# GateAmp.net
KiCad netlist of a schematic drawn in Altium Designer
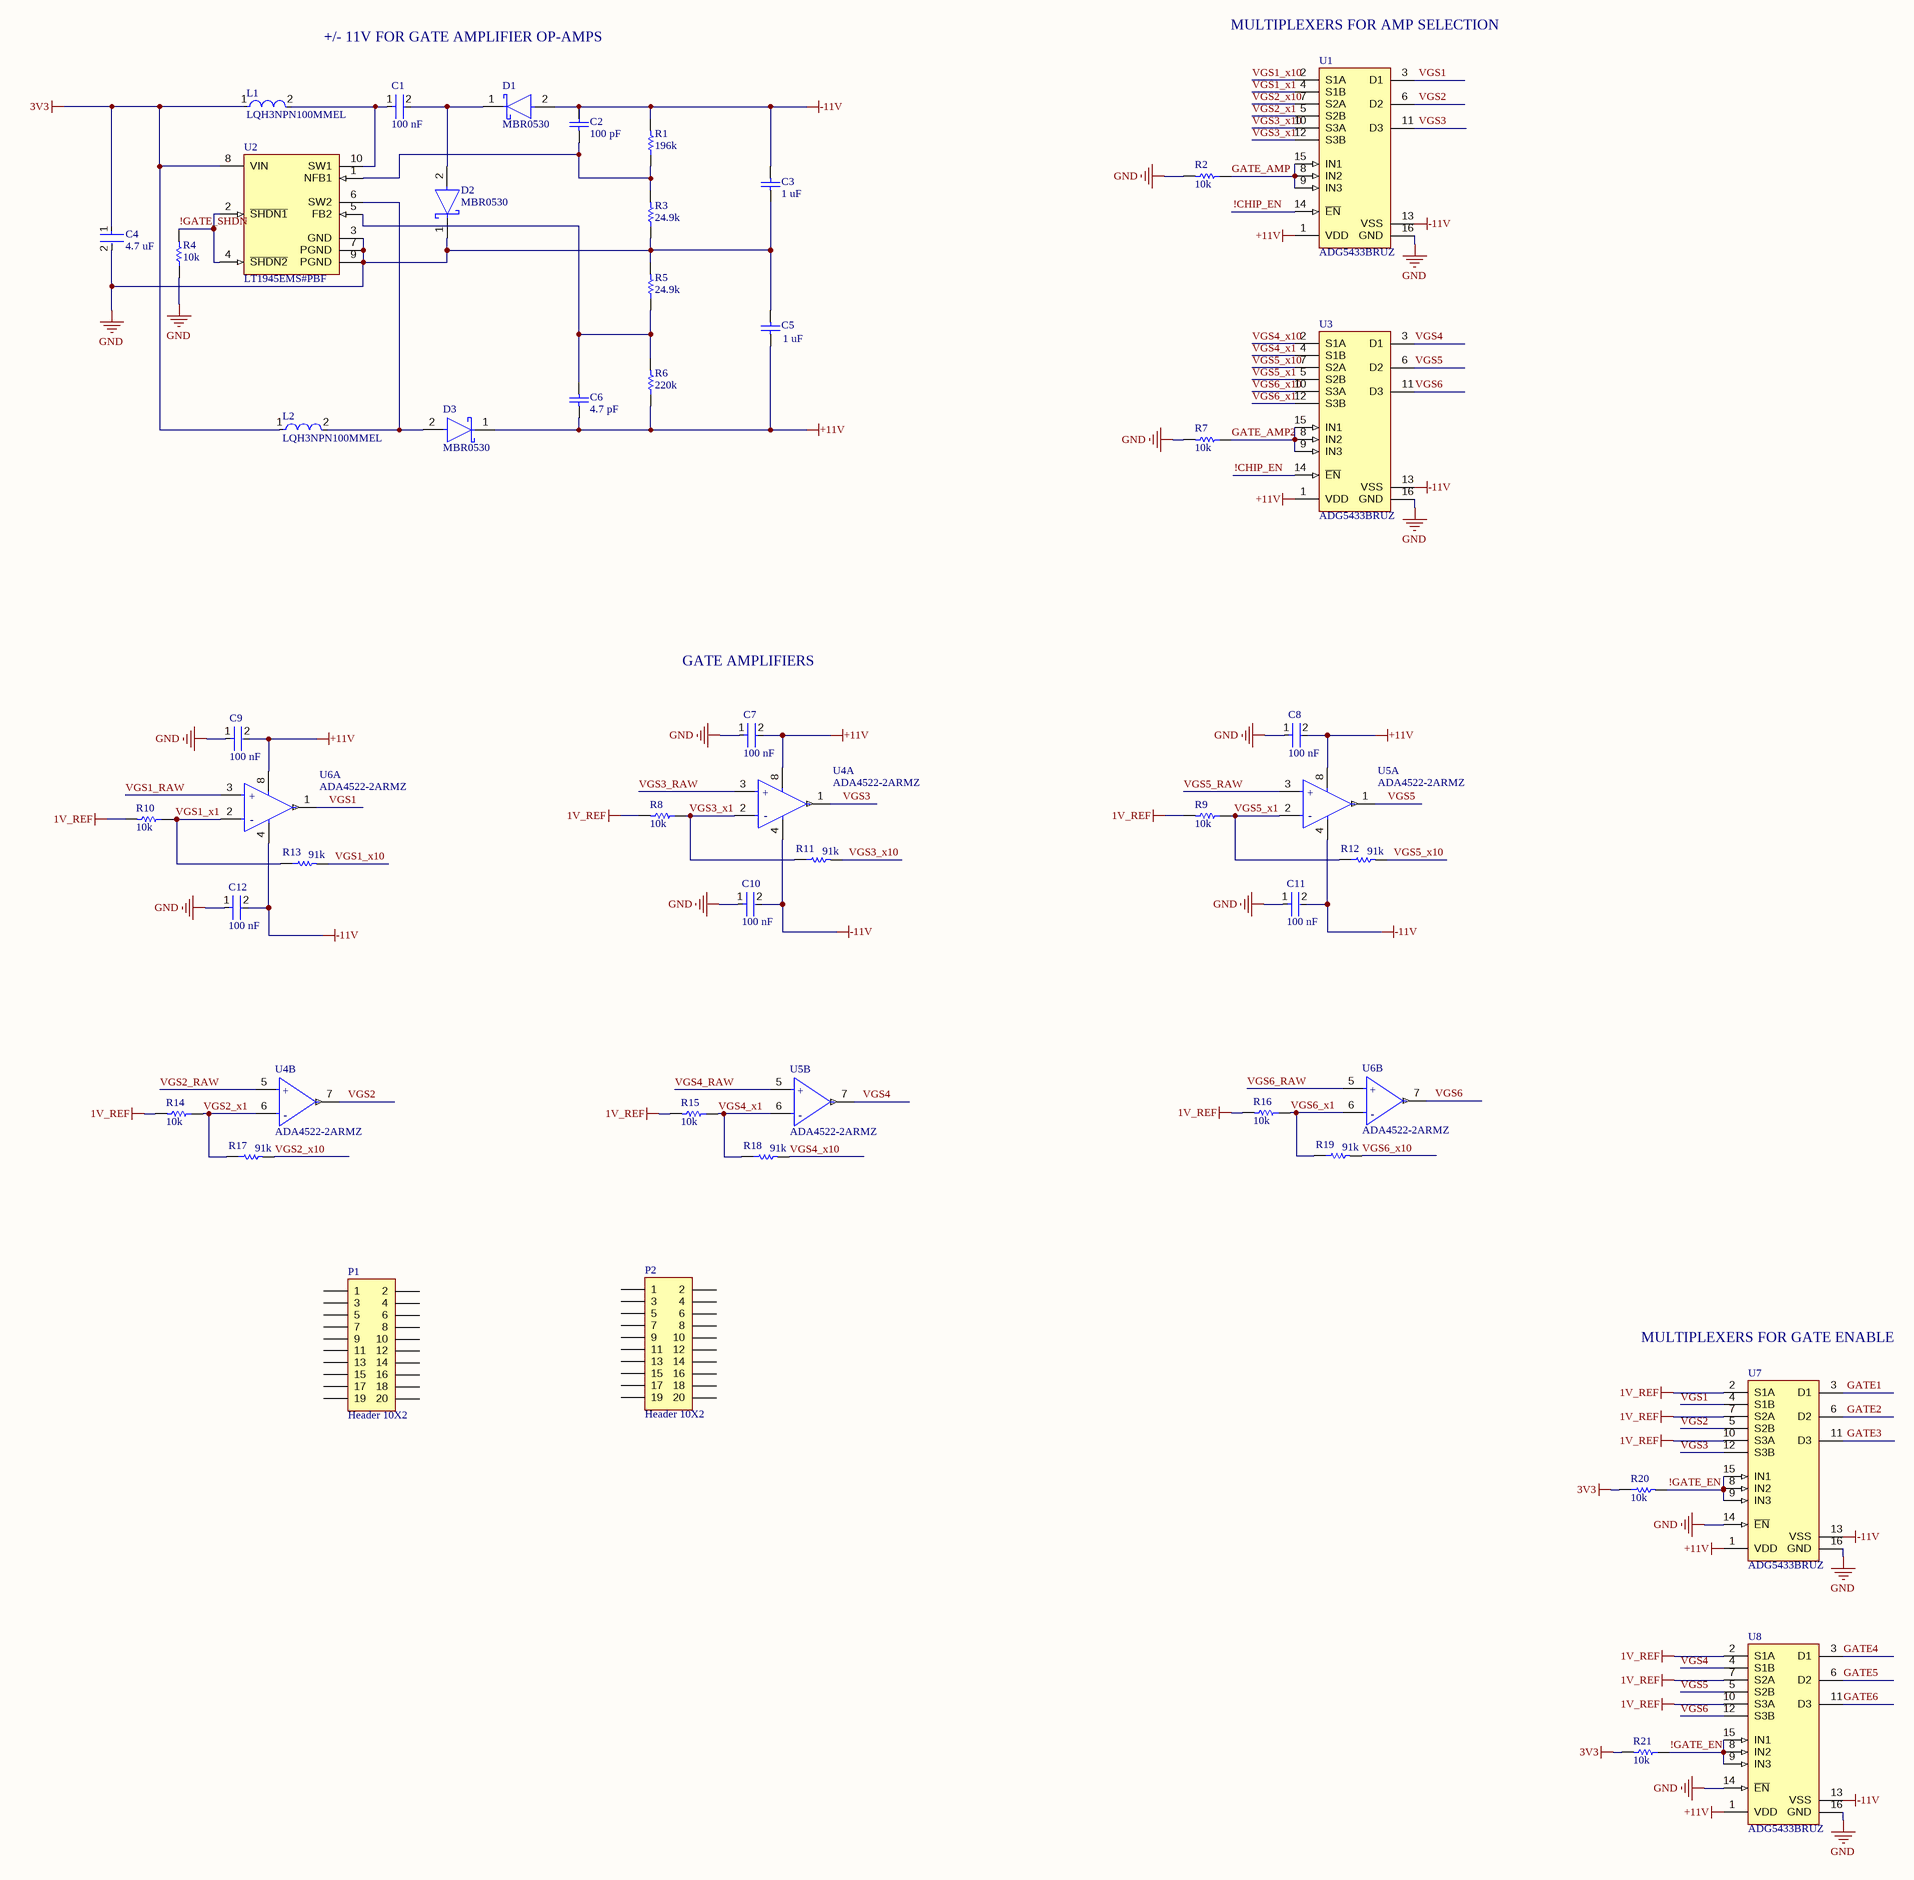
[diagram p0: GateAmp.SchDoc]

(export (version "E")
  (design (tool "Eeschema 10.0.6"))
  (components
    (comp (ref "C1")
      (value "100 nF")
      (footprint "FP-C0805C-DN-MFG")
      (description "CAP CER 0.1UF 50V X7R 0805")
      (fields
        (field (name "MANUFACTURER PART NUMBER") "C0805C104K5RACTU")
        (field (name "MANUFACTURER") "KEMET")
      )
      (libsource (lib "Altium Content Vault") (part "b4654b650e69147ec39a6b967a45e02"))
    )
    (comp (ref "C2")
      (value "100 pF")
      (footprint "CAPC2013X140X50ML20T25")
      (description "08055C101KAT2A")
      (fields (field (name "MANUFACTURER") "AVX Interconnect / Elco"))
      (libsource (lib "Altium Content Vault") (part "CAP"))
    )
    (comp (ref "C3")
      (value "1 uF")
      (footprint "CAPC3216X110X50LL20T25")
      (description "C1206C105K5RACTU")
      (fields (field (name "MANUFACTURER") "Kemet") (field (name "TOLERANCE") "10%"))
      (libsource (lib "Altium Content Vault") (part "CAP-NP-2"))
    )
    (comp (ref "C4")
      (value "4.7 uF")
      (footprint "FP-C0805C475K3PACTU-MFG")
      (description "CAP CER 4.7UF 25V X5R 0805")
      (fields (field (name "TOLERANCE") "10%") (field (name "VOLTAGE") "25V"))
      (libsource (lib "Altium Content Vault") (part "02cd4be3c70576c341d710602a673aa"))
    )
    (comp (ref "C5")
      (value "1 uF")
      (footprint "CAPC3216X110X50LL20T25")
      (description "C1206C105K5RACTU")
      (fields (field (name "MANUFACTURER") "Kemet") (field (name "TOLERANCE") "10%"))
      (libsource (lib "Altium Content Vault") (part "CAP-NP-2"))
    )
    (comp (ref "C6")
      (value "4.7 pF")
      (footprint "CAPC2013X71X50ML20T25")
      (description "08055A4R7CAT2A")
      (fields (field (name "MANUFACTURER") "AVX Interconnect / Elco"))
      (libsource (lib "Altium Content Vault") (part "CAP"))
    )
    (comp (ref "C7")
      (value "100 nF")
      (footprint "FP-C0805C-DN-MFG")
      (description "CAP CER 0.1UF 50V X7R 0805")
      (fields
        (field (name "MANUFACTURER PART NUMBER") "C0805C104K5RACTU")
        (field (name "MANUFACTURER") "KEMET")
      )
      (libsource (lib "Altium Content Vault") (part "b4654b650e69147ec39a6b967a45e02"))
    )
    (comp (ref "C8")
      (value "100 nF")
      (footprint "FP-C0805C-DN-MFG")
      (description "CAP CER 0.1UF 50V X7R 0805")
      (fields
        (field (name "MANUFACTURER PART NUMBER") "C0805C104K5RACTU")
        (field (name "MANUFACTURER") "KEMET")
      )
      (libsource (lib "Altium Content Vault") (part "b4654b650e69147ec39a6b967a45e02"))
    )
    (comp (ref "C9")
      (value "100 nF")
      (footprint "FP-C0805C-DN-MFG")
      (description "CAP CER 0.1UF 50V X7R 0805")
      (fields
        (field (name "MANUFACTURER PART NUMBER") "C0805C104K5RACTU")
        (field (name "MANUFACTURER") "KEMET")
      )
      (libsource (lib "Altium Content Vault") (part "b4654b650e69147ec39a6b967a45e02"))
    )
    (comp (ref "C10")
      (value "100 nF")
      (footprint "FP-C0805C-DN-MFG")
      (description "CAP CER 0.1UF 50V X7R 0805")
      (fields
        (field (name "MANUFACTURER PART NUMBER") "C0805C104K5RACTU")
        (field (name "MANUFACTURER") "KEMET")
      )
      (libsource (lib "Altium Content Vault") (part "b4654b650e69147ec39a6b967a45e02"))
    )
    (comp (ref "C11")
      (value "100 nF")
      (footprint "FP-C0805C-DN-MFG")
      (description "CAP CER 0.1UF 50V X7R 0805")
      (fields
        (field (name "MANUFACTURER PART NUMBER") "C0805C104K5RACTU")
        (field (name "MANUFACTURER") "KEMET")
      )
      (libsource (lib "Altium Content Vault") (part "b4654b650e69147ec39a6b967a45e02"))
    )
    (comp (ref "C12")
      (value "100 nF")
      (footprint "FP-C0805C-DN-MFG")
      (description "CAP CER 0.1UF 50V X7R 0805")
      (fields
        (field (name "MANUFACTURER PART NUMBER") "C0805C104K5RACTU")
        (field (name "MANUFACTURER") "KEMET")
      )
      (libsource (lib "Altium Content Vault") (part "b4654b650e69147ec39a6b967a45e02"))
    )
    (comp (ref "D1")
      (value "MBR0530")
      (footprint "FP-425-04-MFG")
      (description "DIODE SCHOTTKY 30V 500MA SOD123")
      (libsource (lib "Altium Content Vault") (part "1d6ec82d83fb6aee721767c19dac4b9"))
    )
    (comp (ref "D2")
      (value "MBR0530")
      (footprint "FP-425-04-MFG")
      (description "DIODE SCHOTTKY 30V 500MA SOD123")
      (libsource (lib "Altium Content Vault") (part "1d6ec82d83fb6aee721767c19dac4b9"))
    )
    (comp (ref "D3")
      (value "MBR0530")
      (footprint "FP-425-04-MFG")
      (description "DIODE SCHOTTKY 30V 500MA SOD123")
      (libsource (lib "Altium Content Vault") (part "1d6ec82d83fb6aee721767c19dac4b9"))
    )
    (comp (ref "L1")
      (value "LQH3NPN100MMEL")
      (footprint "FP-LQH3NPH_ME-MFG")
      (description "Wire Wound Ferrite Inductor for Power Lines 10μH ±20% 0.228Ω 1280mA 1212")
      (fields (field (name "TOLERANCE") "20%"))
      (libsource (lib "Altium Content Vault") (part "725321dda6339637d4d059423bc1c3c"))
    )
    (comp (ref "L2")
      (value "LQH3NPN100MMEL")
      (footprint "FP-LQH3NPH_ME-MFG")
      (description "Wire Wound Ferrite Inductor for Power Lines 10μH ±20% 0.228Ω 1280mA 1212")
      (fields (field (name "TOLERANCE") "20%"))
      (libsource (lib "Altium Content Vault") (part "725321dda6339637d4d059423bc1c3c"))
    )
    (comp (ref "P1")
      (value "Header 10X2")
      (footprint "HDR2X10")
      (description "Header, 10-Pin, Dual row")
      (fields (field (name "PUBLISHER") "Altium Limited"))
      (libsource (lib "Miscellaneous Connectors") (part "Header 10X2"))
    )
    (comp (ref "P2")
      (value "Header 10X2")
      (footprint "HDR2X10")
      (description "Header, 10-Pin, Dual row")
      (fields (field (name "PUBLISHER") "Altium Limited"))
      (libsource (lib "Miscellaneous Connectors") (part "Header 10X2"))
    )
    (comp (ref "R1")
      (value "196k")
      (footprint "RESC2013X50X30LL20T20")
      (fields (field (name "MANUFACTURER") "Vishay Dale") (field (name "PART NUMBER") "CRCW0805196KFKEA"))
      (libsource (lib "Altium Content Vault") (part "RES"))
    )
    (comp (ref "R2")
      (value "10k")
      (footprint "RESC2013X60X35NL10T20")
      (description "Chip Resistor, 10 KOhm, +/- 1%, 0.125 W, -55 to 155 degC, 0805 (2012 Metric), RoHS, Tape and Reel")
      (fields (field (name "MANUFACTURER") "Yageo"))
      (libsource (lib "Altium Content Vault") (part "RES-2"))
    )
    (comp (ref "R3")
      (value "24.9k")
      (footprint "RESC2013X70X40LL20T20")
      (fields (field (name "PART NUMBER") "ERJ-6ENF2492V") (field (name "MANUFACTURER") "Panasonic"))
      (libsource (lib "Altium Content Vault") (part "RES"))
    )
    (comp (ref "R4")
      (value "10k")
      (footprint "RESC2013X60X35NL10T20")
      (description "Chip Resistor, 10 KOhm, +/- 1%, 0.125 W, -55 to 155 degC, 0805 (2012 Metric), RoHS, Tape and Reel")
      (fields (field (name "MANUFACTURER") "Yageo"))
      (libsource (lib "Altium Content Vault") (part "RES-2"))
    )
    (comp (ref "R5")
      (value "24.9k")
      (footprint "RESC2013X70X40LL20T20")
      (fields (field (name "PART NUMBER") "ERJ-6ENF2492V") (field (name "MANUFACTURER") "Panasonic"))
      (libsource (lib "Altium Content Vault") (part "RES"))
    )
    (comp (ref "R6")
      (value "220k")
      (footprint "RESC2013X70X40ML20T20")
      (fields (field (name "PART NUMBER") "ERJ6ENF2203V") (field (name "MANUFACTURER") "Panasonic"))
      (libsource (lib "Altium Content Vault") (part "RES"))
    )
    (comp (ref "R7")
      (value "10k")
      (footprint "RESC2013X60X35NL10T20")
      (description "Chip Resistor, 10 KOhm, +/- 1%, 0.125 W, -55 to 155 degC, 0805 (2012 Metric), RoHS, Tape and Reel")
      (fields (field (name "MANUFACTURER") "Yageo"))
      (libsource (lib "Altium Content Vault") (part "RES-2"))
    )
    (comp (ref "R8")
      (value "10k")
      (footprint "RESC2013X60X35NL10T20")
      (description "Chip Resistor, 10 KOhm, +/- 1%, 0.125 W, -55 to 155 degC, 0805 (2012 Metric), RoHS, Tape and Reel")
      (fields (field (name "MANUFACTURER") "Yageo"))
      (libsource (lib "Altium Content Vault") (part "RES-2"))
    )
    (comp (ref "R9")
      (value "10k")
      (footprint "RESC2013X60X35NL10T20")
      (description "Chip Resistor, 10 KOhm, +/- 1%, 0.125 W, -55 to 155 degC, 0805 (2012 Metric), RoHS, Tape and Reel")
      (fields (field (name "MANUFACTURER") "Yageo"))
      (libsource (lib "Altium Content Vault") (part "RES-2"))
    )
    (comp (ref "R10")
      (value "10k")
      (footprint "RESC2013X60X35NL10T20")
      (description "Chip Resistor, 10 KOhm, +/- 1%, 0.125 W, -55 to 155 degC, 0805 (2012 Metric), RoHS, Tape and Reel")
      (fields (field (name "MANUFACTURER") "Yageo"))
      (libsource (lib "Altium Content Vault") (part "RES-2"))
    )
    (comp (ref "R11")
      (value "91k")
      (footprint "RESC2013X60X40LL20T25")
      (fields (field (name "PART NUMBER") "ERA6AEB913V") (field (name "MANUFACTURER") "Panasonic"))
      (libsource (lib "Altium Content Vault") (part "RES"))
    )
    (comp (ref "R12")
      (value "91k")
      (footprint "RESC2013X60X40LL20T25")
      (fields (field (name "PART NUMBER") "ERA6AEB913V") (field (name "MANUFACTURER") "Panasonic"))
      (libsource (lib "Altium Content Vault") (part "RES"))
    )
    (comp (ref "R13")
      (value "91k")
      (footprint "RESC2013X60X40LL20T25")
      (fields (field (name "PART NUMBER") "ERA6AEB913V") (field (name "MANUFACTURER") "Panasonic"))
      (libsource (lib "Altium Content Vault") (part "RES"))
    )
    (comp (ref "R14")
      (value "10k")
      (footprint "RESC2013X60X35NL10T20")
      (description "Chip Resistor, 10 KOhm, +/- 1%, 0.125 W, -55 to 155 degC, 0805 (2012 Metric), RoHS, Tape and Reel")
      (fields (field (name "MANUFACTURER") "Yageo"))
      (libsource (lib "Altium Content Vault") (part "RES-2"))
    )
    (comp (ref "R15")
      (value "10k")
      (footprint "RESC2013X60X35NL10T20")
      (description "Chip Resistor, 10 KOhm, +/- 1%, 0.125 W, -55 to 155 degC, 0805 (2012 Metric), RoHS, Tape and Reel")
      (fields (field (name "MANUFACTURER") "Yageo"))
      (libsource (lib "Altium Content Vault") (part "RES-2"))
    )
    (comp (ref "R16")
      (value "10k")
      (footprint "RESC2013X60X35NL10T20")
      (description "Chip Resistor, 10 KOhm, +/- 1%, 0.125 W, -55 to 155 degC, 0805 (2012 Metric), RoHS, Tape and Reel")
      (fields (field (name "MANUFACTURER") "Yageo"))
      (libsource (lib "Altium Content Vault") (part "RES-2"))
    )
    (comp (ref "R17")
      (value "91k")
      (footprint "RESC2013X60X40LL20T25")
      (fields (field (name "PART NUMBER") "ERA6AEB913V") (field (name "MANUFACTURER") "Panasonic"))
      (libsource (lib "Altium Content Vault") (part "RES"))
    )
    (comp (ref "R18")
      (value "91k")
      (footprint "RESC2013X60X40LL20T25")
      (fields (field (name "PART NUMBER") "ERA6AEB913V") (field (name "MANUFACTURER") "Panasonic"))
      (libsource (lib "Altium Content Vault") (part "RES"))
    )
    (comp (ref "R19")
      (value "91k")
      (footprint "RESC2013X60X40LL20T25")
      (fields (field (name "PART NUMBER") "ERA6AEB913V") (field (name "MANUFACTURER") "Panasonic"))
      (libsource (lib "Altium Content Vault") (part "RES"))
    )
    (comp (ref "R20")
      (value "10k")
      (footprint "RESC2013X60X35NL10T20")
      (description "Chip Resistor, 10 KOhm, +/- 1%, 0.125 W, -55 to 155 degC, 0805 (2012 Metric), RoHS, Tape and Reel")
      (fields (field (name "MANUFACTURER") "Yageo"))
      (libsource (lib "Altium Content Vault") (part "RES-2"))
    )
    (comp (ref "R21")
      (value "10k")
      (footprint "RESC2013X60X35NL10T20")
      (description "Chip Resistor, 10 KOhm, +/- 1%, 0.125 W, -55 to 155 degC, 0805 (2012 Metric), RoHS, Tape and Reel")
      (fields (field (name "MANUFACTURER") "Yageo"))
      (libsource (lib "Altium Content Vault") (part "RES-2"))
    )
    (comp (ref "U1")
      (value "ADG5433BRUZ")
      (footprint "ADI-RU-16_N")
      (description "High Voltage Latch-Up Proof, Triple SPDT Switches, 12.5 Ohm Ron, 16-pin SOP (RU-16), Tube")
      (fields (field (name "MANUFACTURER") "Analog Devices"))
      (libsource (lib "Altium Content Vault") (part "ADI-ADG5433-RU-16"))
    )
    (comp (ref "U2")
      (value "LT1945EMS#PBF")
      (footprint "LT-MS-10_N")
      (fields (field (name "MANUFACTURER") "Linear Technology"))
      (libsource (lib "Altium Content Vault") (part "LT-LT1945-MS-10"))
    )
    (comp (ref "U3")
      (value "ADG5433BRUZ")
      (footprint "ADI-RU-16_N")
      (description "High Voltage Latch-Up Proof, Triple SPDT Switches, 12.5 Ohm Ron, 16-pin SOP (RU-16), Tube")
      (fields (field (name "MANUFACTURER") "Analog Devices"))
      (libsource (lib "Altium Content Vault") (part "ADI-ADG5433-RU-16"))
    )
    (comp (ref "U4")
      (value "ADA4522-2ARMZ")
      (footprint "FP-RM-8-IPC_C")
      (description "IC OPAMP ZERO-DRIFT 2 CIRC 8MSOP")
      (libsource (lib "Altium Content Vault") (part "e8c52d48d03680a0ba04c611cf3b55d"))
    )
    (comp (ref "U5")
      (value "ADA4522-2ARMZ")
      (footprint "FP-RM-8-IPC_C")
      (description "IC OPAMP ZERO-DRIFT 2 CIRC 8MSOP")
      (libsource (lib "Altium Content Vault") (part "e8c52d48d03680a0ba04c611cf3b55d"))
    )
    (comp (ref "U6")
      (value "ADA4522-2ARMZ")
      (footprint "FP-RM-8-IPC_C")
      (description "IC OPAMP ZERO-DRIFT 2 CIRC 8MSOP")
      (libsource (lib "Altium Content Vault") (part "e8c52d48d03680a0ba04c611cf3b55d"))
    )
    (comp (ref "U7")
      (value "ADG5433BRUZ")
      (footprint "ADI-RU-16_N")
      (description "High Voltage Latch-Up Proof, Triple SPDT Switches, 12.5 Ohm Ron, 16-pin SOP (RU-16), Tube")
      (fields (field (name "MANUFACTURER") "Analog Devices"))
      (libsource (lib "Altium Content Vault") (part "ADI-ADG5433-RU-16"))
    )
    (comp (ref "U8")
      (value "ADG5433BRUZ")
      (footprint "ADI-RU-16_N")
      (description "High Voltage Latch-Up Proof, Triple SPDT Switches, 12.5 Ohm Ron, 16-pin SOP (RU-16), Tube")
      (fields (field (name "MANUFACTURER") "Analog Devices"))
      (libsource (lib "Altium Content Vault") (part "ADI-ADG5433-RU-16"))
    )
  )
  (nets
    (net (code "1") (name "+11V") (class "Default")
      (node (ref "C5") (pin "1") (pinfunction "1_1") (pintype "passive"))
      (node (ref "C6") (pin "1") (pinfunction "1_1") (pintype "passive"))
      (node (ref "C7") (pin "2") (pinfunction "2_2") (pintype "passive"))
      (node (ref "C8") (pin "2") (pinfunction "2_2") (pintype "passive"))
      (node (ref "C9") (pin "2") (pinfunction "2_2") (pintype "passive"))
      (node (ref "D3") (pin "1") (pinfunction "C_1") (pintype "passive"))
      (node (ref "R6") (pin "1") (pinfunction "1_1") (pintype "passive"))
      (node (ref "U1") (pin "1") (pinfunction "VDD_1") (pintype "power_in"))
      (node (ref "U3") (pin "1") (pinfunction "VDD_1") (pintype "power_in"))
      (node (ref "U4") (pin "8") (pinfunction "V+_8") (pintype "power_in"))
      (node (ref "U5") (pin "8") (pinfunction "V+_8") (pintype "power_in"))
      (node (ref "U6") (pin "8") (pinfunction "V+_8") (pintype "power_in"))
      (node (ref "U7") (pin "1") (pinfunction "VDD_1") (pintype "power_in"))
      (node (ref "U8") (pin "1") (pinfunction "VDD_1") (pintype "power_in"))
    )
    (net (code "2") (name "-11V") (class "Default")
      (node (ref "C10") (pin "2") (pinfunction "2_2") (pintype "passive"))
      (node (ref "C11") (pin "2") (pinfunction "2_2") (pintype "passive"))
      (node (ref "C12") (pin "2") (pinfunction "2_2") (pintype "passive"))
      (node (ref "C2") (pin "1") (pinfunction "1_1") (pintype "passive"))
      (node (ref "C3") (pin "2") (pinfunction "2_2") (pintype "passive"))
      (node (ref "D1") (pin "2") (pinfunction "A_2") (pintype "passive"))
      (node (ref "R1") (pin "2") (pinfunction "2_2") (pintype "passive"))
      (node (ref "U1") (pin "13") (pinfunction "VSS_13") (pintype "power_in"))
      (node (ref "U3") (pin "13") (pinfunction "VSS_13") (pintype "power_in"))
      (node (ref "U4") (pin "4") (pinfunction "V-_4") (pintype "power_in"))
      (node (ref "U5") (pin "4") (pinfunction "V-_4") (pintype "power_in"))
      (node (ref "U6") (pin "4") (pinfunction "V-_4") (pintype "power_in"))
      (node (ref "U7") (pin "13") (pinfunction "VSS_13") (pintype "power_in"))
      (node (ref "U8") (pin "13") (pinfunction "VSS_13") (pintype "power_in"))
    )
    (net (code "3") (name "/!CHIP_EN") (class "Default")
      (node (ref "U1") (pin "14") (pinfunction "~{EN}_14") (pintype "input"))
      (node (ref "U3") (pin "14") (pinfunction "~{EN}_14") (pintype "input"))
    )
    (net (code "4") (name "/!GATE_EN") (class "Default")
      (node (ref "R20") (pin "2") (pinfunction "2_2") (pintype "passive"))
      (node (ref "R21") (pin "1") (pinfunction "1_1") (pintype "passive"))
      (node (ref "U7") (pin "15") (pinfunction "IN1_15") (pintype "input"))
      (node (ref "U7") (pin "8") (pinfunction "IN2_8") (pintype "input"))
      (node (ref "U7") (pin "9") (pinfunction "IN3_9") (pintype "input"))
      (node (ref "U8") (pin "15") (pinfunction "IN1_15") (pintype "input"))
      (node (ref "U8") (pin "8") (pinfunction "IN2_8") (pintype "input"))
      (node (ref "U8") (pin "9") (pinfunction "IN3_9") (pintype "input"))
    )
    (net (code "5") (name "/!GATE_SHDN") (class "Default")
      (node (ref "R4") (pin "2") (pinfunction "2_2") (pintype "passive"))
      (node (ref "U2") (pin "2") (pinfunction "~{SHDN1}_2") (pintype "input"))
      (node (ref "U2") (pin "4") (pinfunction "~{SHDN2}_4") (pintype "input"))
    )
    (net (code "6") (name "/GATE1") (class "Default")
      (node (ref "U7") (pin "3") (pinfunction "D1_3") (pintype "passive"))
    )
    (net (code "7") (name "/GATE2") (class "Default")
      (node (ref "U7") (pin "6") (pinfunction "D2_6") (pintype "passive"))
    )
    (net (code "8") (name "/GATE3") (class "Default")
      (node (ref "U7") (pin "11") (pinfunction "D3_11") (pintype "passive"))
    )
    (net (code "9") (name "/GATE4") (class "Default")
      (node (ref "U8") (pin "3") (pinfunction "D1_3") (pintype "passive"))
    )
    (net (code "10") (name "/GATE5") (class "Default")
      (node (ref "U8") (pin "6") (pinfunction "D2_6") (pintype "passive"))
    )
    (net (code "11") (name "/GATE6") (class "Default")
      (node (ref "U8") (pin "11") (pinfunction "D3_11") (pintype "passive"))
    )
    (net (code "12") (name "/GATE_AMP") (class "Default")
      (node (ref "R2") (pin "1") (pinfunction "1_1") (pintype "passive"))
      (node (ref "U1") (pin "15") (pinfunction "IN1_15") (pintype "input"))
      (node (ref "U1") (pin "8") (pinfunction "IN2_8") (pintype "input"))
      (node (ref "U1") (pin "9") (pinfunction "IN3_9") (pintype "input"))
    )
    (net (code "13") (name "/GATE_AMP2") (class "Default")
      (node (ref "R7") (pin "1") (pinfunction "1_1") (pintype "passive"))
      (node (ref "U3") (pin "15") (pinfunction "IN1_15") (pintype "input"))
      (node (ref "U3") (pin "8") (pinfunction "IN2_8") (pintype "input"))
      (node (ref "U3") (pin "9") (pinfunction "IN3_9") (pintype "input"))
    )
    (net (code "14") (name "/VGS1") (class "Default")
      (node (ref "U1") (pin "3") (pinfunction "D1_3") (pintype "passive"))
      (node (ref "U6") (pin "1") (pinfunction "OUT_A_1") (pintype "output"))
      (node (ref "U7") (pin "4") (pinfunction "S1B_4") (pintype "passive"))
    )
    (net (code "15") (name "/VGS1_RAW") (class "Default")
      (node (ref "U6") (pin "3") (pinfunction "+IN_A_3") (pintype "tri_state"))
    )
    (net (code "16") (name "/VGS1_x1") (class "Default")
      (node (ref "R10") (pin "1") (pinfunction "1_1") (pintype "passive"))
      (node (ref "R13") (pin "1") (pinfunction "1_1") (pintype "passive"))
      (node (ref "U1") (pin "4") (pinfunction "S1B_4") (pintype "passive"))
      (node (ref "U6") (pin "2") (pinfunction "-IN_A_2") (pintype "tri_state"))
    )
    (net (code "17") (name "/VGS1_x10") (class "Default")
      (node (ref "R13") (pin "2") (pinfunction "2_2") (pintype "passive"))
      (node (ref "U1") (pin "2") (pinfunction "S1A_2") (pintype "passive"))
    )
    (net (code "18") (name "/VGS2") (class "Default")
      (node (ref "U1") (pin "6") (pinfunction "D2_6") (pintype "passive"))
      (node (ref "U4") (pin "7") (pinfunction "OUT_B_7") (pintype "output"))
      (node (ref "U7") (pin "5") (pinfunction "S2B_5") (pintype "passive"))
    )
    (net (code "19") (name "/VGS2_RAW") (class "Default")
      (node (ref "U4") (pin "5") (pinfunction "+IN_B_5") (pintype "tri_state"))
    )
    (net (code "20") (name "/VGS2_x1") (class "Default")
      (node (ref "R14") (pin "1") (pinfunction "1_1") (pintype "passive"))
      (node (ref "R17") (pin "1") (pinfunction "1_1") (pintype "passive"))
      (node (ref "U1") (pin "5") (pinfunction "S2B_5") (pintype "passive"))
      (node (ref "U4") (pin "6") (pinfunction "-IN_B_6") (pintype "tri_state"))
    )
    (net (code "21") (name "/VGS2_x10") (class "Default")
      (node (ref "R17") (pin "2") (pinfunction "2_2") (pintype "passive"))
      (node (ref "U1") (pin "7") (pinfunction "S2A_7") (pintype "passive"))
    )
    (net (code "22") (name "/VGS3") (class "Default")
      (node (ref "U1") (pin "11") (pinfunction "D3_11") (pintype "passive"))
      (node (ref "U4") (pin "1") (pinfunction "OUT_A_1") (pintype "output"))
      (node (ref "U7") (pin "12") (pinfunction "S3B_12") (pintype "passive"))
    )
    (net (code "23") (name "/VGS3_RAW") (class "Default")
      (node (ref "U4") (pin "3") (pinfunction "+IN_A_3") (pintype "tri_state"))
    )
    (net (code "24") (name "/VGS3_x1") (class "Default")
      (node (ref "R11") (pin "1") (pinfunction "1_1") (pintype "passive"))
      (node (ref "R8") (pin "1") (pinfunction "1_1") (pintype "passive"))
      (node (ref "U1") (pin "12") (pinfunction "S3B_12") (pintype "passive"))
      (node (ref "U4") (pin "2") (pinfunction "-IN_A_2") (pintype "tri_state"))
    )
    (net (code "25") (name "/VGS3_x10") (class "Default")
      (node (ref "R11") (pin "2") (pinfunction "2_2") (pintype "passive"))
      (node (ref "U1") (pin "10") (pinfunction "S3A_10") (pintype "passive"))
    )
    (net (code "26") (name "/VGS4") (class "Default")
      (node (ref "U3") (pin "3") (pinfunction "D1_3") (pintype "passive"))
      (node (ref "U5") (pin "7") (pinfunction "OUT_B_7") (pintype "output"))
      (node (ref "U8") (pin "4") (pinfunction "S1B_4") (pintype "passive"))
    )
    (net (code "27") (name "/VGS4_RAW") (class "Default")
      (node (ref "U5") (pin "5") (pinfunction "+IN_B_5") (pintype "tri_state"))
    )
    (net (code "28") (name "/VGS4_x1") (class "Default")
      (node (ref "R15") (pin "1") (pinfunction "1_1") (pintype "passive"))
      (node (ref "R18") (pin "1") (pinfunction "1_1") (pintype "passive"))
      (node (ref "U3") (pin "4") (pinfunction "S1B_4") (pintype "passive"))
      (node (ref "U5") (pin "6") (pinfunction "-IN_B_6") (pintype "tri_state"))
    )
    (net (code "29") (name "/VGS4_x10") (class "Default")
      (node (ref "R18") (pin "2") (pinfunction "2_2") (pintype "passive"))
      (node (ref "U3") (pin "2") (pinfunction "S1A_2") (pintype "passive"))
    )
    (net (code "30") (name "/VGS5") (class "Default")
      (node (ref "U3") (pin "6") (pinfunction "D2_6") (pintype "passive"))
      (node (ref "U5") (pin "1") (pinfunction "OUT_A_1") (pintype "output"))
      (node (ref "U8") (pin "5") (pinfunction "S2B_5") (pintype "passive"))
    )
    (net (code "31") (name "/VGS5_RAW") (class "Default")
      (node (ref "U5") (pin "3") (pinfunction "+IN_A_3") (pintype "tri_state"))
    )
    (net (code "32") (name "/VGS5_x1") (class "Default")
      (node (ref "R12") (pin "1") (pinfunction "1_1") (pintype "passive"))
      (node (ref "R9") (pin "1") (pinfunction "1_1") (pintype "passive"))
      (node (ref "U3") (pin "5") (pinfunction "S2B_5") (pintype "passive"))
      (node (ref "U5") (pin "2") (pinfunction "-IN_A_2") (pintype "tri_state"))
    )
    (net (code "33") (name "/VGS5_x10") (class "Default")
      (node (ref "R12") (pin "2") (pinfunction "2_2") (pintype "passive"))
      (node (ref "U3") (pin "7") (pinfunction "S2A_7") (pintype "passive"))
    )
    (net (code "34") (name "/VGS6") (class "Default")
      (node (ref "U3") (pin "11") (pinfunction "D3_11") (pintype "passive"))
      (node (ref "U6") (pin "7") (pinfunction "OUT_B_7") (pintype "output"))
      (node (ref "U8") (pin "12") (pinfunction "S3B_12") (pintype "passive"))
    )
    (net (code "35") (name "/VGS6_RAW") (class "Default")
      (node (ref "U6") (pin "5") (pinfunction "+IN_B_5") (pintype "tri_state"))
    )
    (net (code "36") (name "/VGS6_x1") (class "Default")
      (node (ref "R16") (pin "1") (pinfunction "1_1") (pintype "passive"))
      (node (ref "R19") (pin "1") (pinfunction "1_1") (pintype "passive"))
      (node (ref "U3") (pin "12") (pinfunction "S3B_12") (pintype "passive"))
      (node (ref "U6") (pin "6") (pinfunction "-IN_B_6") (pintype "tri_state"))
    )
    (net (code "37") (name "/VGS6_x10") (class "Default")
      (node (ref "R19") (pin "2") (pinfunction "2_2") (pintype "passive"))
      (node (ref "U3") (pin "10") (pinfunction "S3A_10") (pintype "passive"))
    )
    (net (code "38") (name "1V_REF") (class "Default")
      (node (ref "R10") (pin "2") (pinfunction "2_2") (pintype "passive"))
      (node (ref "R14") (pin "2") (pinfunction "2_2") (pintype "passive"))
      (node (ref "R15") (pin "2") (pinfunction "2_2") (pintype "passive"))
      (node (ref "R16") (pin "2") (pinfunction "2_2") (pintype "passive"))
      (node (ref "R8") (pin "2") (pinfunction "2_2") (pintype "passive"))
      (node (ref "R9") (pin "2") (pinfunction "2_2") (pintype "passive"))
      (node (ref "U7") (pin "10") (pinfunction "S3A_10") (pintype "passive"))
      (node (ref "U7") (pin "2") (pinfunction "S1A_2") (pintype "passive"))
      (node (ref "U7") (pin "7") (pinfunction "S2A_7") (pintype "passive"))
      (node (ref "U8") (pin "10") (pinfunction "S3A_10") (pintype "passive"))
      (node (ref "U8") (pin "2") (pinfunction "S1A_2") (pintype "passive"))
      (node (ref "U8") (pin "7") (pinfunction "S2A_7") (pintype "passive"))
    )
    (net (code "39") (name "3V3") (class "Default")
      (node (ref "C4") (pin "1") (pinfunction "1_1") (pintype "passive"))
      (node (ref "L1") (pin "1") (pinfunction "1_1") (pintype "passive"))
      (node (ref "L2") (pin "1") (pinfunction "1_1") (pintype "passive"))
      (node (ref "R20") (pin "1") (pinfunction "1_1") (pintype "passive"))
      (node (ref "R21") (pin "2") (pinfunction "2_2") (pintype "passive"))
      (node (ref "U2") (pin "8") (pinfunction "VIN_8") (pintype "power_in"))
    )
    (net (code "40") (name "GND") (class "Default")
      (node (ref "C10") (pin "1") (pinfunction "1_1") (pintype "passive"))
      (node (ref "C11") (pin "1") (pinfunction "1_1") (pintype "passive"))
      (node (ref "C12") (pin "1") (pinfunction "1_1") (pintype "passive"))
      (node (ref "C3") (pin "1") (pinfunction "1_1") (pintype "passive"))
      (node (ref "C4") (pin "2") (pinfunction "2_2") (pintype "passive"))
      (node (ref "C5") (pin "2") (pinfunction "2_2") (pintype "passive"))
      (node (ref "C7") (pin "1") (pinfunction "1_1") (pintype "passive"))
      (node (ref "C8") (pin "1") (pinfunction "1_1") (pintype "passive"))
      (node (ref "C9") (pin "1") (pinfunction "1_1") (pintype "passive"))
      (node (ref "D2") (pin "1") (pinfunction "C_1") (pintype "passive"))
      (node (ref "R2") (pin "2") (pinfunction "2_2") (pintype "passive"))
      (node (ref "R3") (pin "1") (pinfunction "1_1") (pintype "passive"))
      (node (ref "R4") (pin "1") (pinfunction "1_1") (pintype "passive"))
      (node (ref "R5") (pin "2") (pinfunction "2_2") (pintype "passive"))
      (node (ref "R7") (pin "2") (pinfunction "2_2") (pintype "passive"))
      (node (ref "U1") (pin "16") (pinfunction "GND_16") (pintype "power_in"))
      (node (ref "U2") (pin "3") (pinfunction "GND_3") (pintype "power_in"))
      (node (ref "U2") (pin "7") (pinfunction "PGND_7") (pintype "power_in"))
      (node (ref "U2") (pin "9") (pinfunction "PGND_9") (pintype "power_in"))
      (node (ref "U3") (pin "16") (pinfunction "GND_16") (pintype "power_in"))
      (node (ref "U7") (pin "14") (pinfunction "~{EN}_14") (pintype "input"))
      (node (ref "U7") (pin "16") (pinfunction "GND_16") (pintype "power_in"))
      (node (ref "U8") (pin "14") (pinfunction "~{EN}_14") (pintype "input"))
      (node (ref "U8") (pin "16") (pinfunction "GND_16") (pintype "power_in"))
    )
    (net (code "41") (name "Net-(D1-C)") (class "Default")
      (node (ref "C1") (pin "2") (pinfunction "2_2") (pintype "passive"))
      (node (ref "D1") (pin "1") (pinfunction "C_1") (pintype "passive"))
      (node (ref "D2") (pin "2") (pinfunction "A_2") (pintype "passive"))
    )
    (net (code "42") (name "Net-(D3-A)") (class "Default")
      (node (ref "D3") (pin "2") (pinfunction "A_2") (pintype "passive"))
      (node (ref "L2") (pin "2") (pinfunction "2_2") (pintype "passive"))
      (node (ref "U2") (pin "6") (pinfunction "SW2_6") (pintype "power_in"))
    )
    (net (code "43") (name "Net-(U2-FB2)") (class "Default")
      (node (ref "C6") (pin "2") (pinfunction "2_2") (pintype "passive"))
      (node (ref "R5") (pin "1") (pinfunction "1_1") (pintype "passive"))
      (node (ref "R6") (pin "2") (pinfunction "2_2") (pintype "passive"))
      (node (ref "U2") (pin "5") (pinfunction "FB2_5") (pintype "input"))
    )
    (net (code "44") (name "Net-(U2-NFB1)") (class "Default")
      (node (ref "C2") (pin "2") (pinfunction "2_2") (pintype "passive"))
      (node (ref "R1") (pin "1") (pinfunction "1_1") (pintype "passive"))
      (node (ref "R3") (pin "2") (pinfunction "2_2") (pintype "passive"))
      (node (ref "U2") (pin "1") (pinfunction "NFB1_1") (pintype "input"))
    )
    (net (code "45") (name "Net-(U2-SW1)") (class "Default")
      (node (ref "C1") (pin "1") (pinfunction "1_1") (pintype "passive"))
      (node (ref "L1") (pin "2") (pinfunction "2_2") (pintype "passive"))
      (node (ref "U2") (pin "10") (pinfunction "SW1_10") (pintype "power_in"))
    )
    (net (code "46") (name "unconnected-(P1-Pad1)") (class "Default")
      (node (ref "P1") (pin "1") (pinfunction "1_1") (pintype "passive"))
    )
    (net (code "47") (name "unconnected-(P1-Pad2)") (class "Default")
      (node (ref "P1") (pin "2") (pinfunction "2_2") (pintype "passive"))
    )
    (net (code "48") (name "unconnected-(P1-Pad3)") (class "Default")
      (node (ref "P1") (pin "3") (pinfunction "3_3") (pintype "passive"))
    )
    (net (code "49") (name "unconnected-(P1-Pad4)") (class "Default")
      (node (ref "P1") (pin "4") (pinfunction "4_4") (pintype "passive"))
    )
    (net (code "50") (name "unconnected-(P1-Pad5)") (class "Default")
      (node (ref "P1") (pin "5") (pinfunction "5_5") (pintype "passive"))
    )
    (net (code "51") (name "unconnected-(P1-Pad6)") (class "Default")
      (node (ref "P1") (pin "6") (pinfunction "6_6") (pintype "passive"))
    )
    (net (code "52") (name "unconnected-(P1-Pad7)") (class "Default")
      (node (ref "P1") (pin "7") (pinfunction "7_7") (pintype "passive"))
    )
    (net (code "53") (name "unconnected-(P1-Pad8)") (class "Default")
      (node (ref "P1") (pin "8") (pinfunction "8_8") (pintype "passive"))
    )
    (net (code "54") (name "unconnected-(P1-Pad9)") (class "Default")
      (node (ref "P1") (pin "9") (pinfunction "9_9") (pintype "passive"))
    )
    (net (code "55") (name "unconnected-(P1-Pad10)") (class "Default")
      (node (ref "P1") (pin "10") (pinfunction "10_10") (pintype "passive"))
    )
    (net (code "56") (name "unconnected-(P1-Pad11)") (class "Default")
      (node (ref "P1") (pin "11") (pinfunction "11_11") (pintype "passive"))
    )
    (net (code "57") (name "unconnected-(P1-Pad12)") (class "Default")
      (node (ref "P1") (pin "12") (pinfunction "12_12") (pintype "passive"))
    )
    (net (code "58") (name "unconnected-(P1-Pad13)") (class "Default")
      (node (ref "P1") (pin "13") (pinfunction "13_13") (pintype "passive"))
    )
    (net (code "59") (name "unconnected-(P1-Pad14)") (class "Default")
      (node (ref "P1") (pin "14") (pinfunction "14_14") (pintype "passive"))
    )
    (net (code "60") (name "unconnected-(P1-Pad15)") (class "Default")
      (node (ref "P1") (pin "15") (pinfunction "15_15") (pintype "passive"))
    )
    (net (code "61") (name "unconnected-(P1-Pad16)") (class "Default")
      (node (ref "P1") (pin "16") (pinfunction "16_16") (pintype "passive"))
    )
    (net (code "62") (name "unconnected-(P1-Pad17)") (class "Default")
      (node (ref "P1") (pin "17") (pinfunction "17_17") (pintype "passive"))
    )
    (net (code "63") (name "unconnected-(P1-Pad18)") (class "Default")
      (node (ref "P1") (pin "18") (pinfunction "18_18") (pintype "passive"))
    )
    (net (code "64") (name "unconnected-(P1-Pad19)") (class "Default")
      (node (ref "P1") (pin "19") (pinfunction "19_19") (pintype "passive"))
    )
    (net (code "65") (name "unconnected-(P1-Pad20)") (class "Default")
      (node (ref "P1") (pin "20") (pinfunction "20_20") (pintype "passive"))
    )
    (net (code "66") (name "unconnected-(P2-Pad1)") (class "Default")
      (node (ref "P2") (pin "1") (pinfunction "1_1") (pintype "passive"))
    )
    (net (code "67") (name "unconnected-(P2-Pad2)") (class "Default")
      (node (ref "P2") (pin "2") (pinfunction "2_2") (pintype "passive"))
    )
    (net (code "68") (name "unconnected-(P2-Pad3)") (class "Default")
      (node (ref "P2") (pin "3") (pinfunction "3_3") (pintype "passive"))
    )
    (net (code "69") (name "unconnected-(P2-Pad4)") (class "Default")
      (node (ref "P2") (pin "4") (pinfunction "4_4") (pintype "passive"))
    )
    (net (code "70") (name "unconnected-(P2-Pad5)") (class "Default")
      (node (ref "P2") (pin "5") (pinfunction "5_5") (pintype "passive"))
    )
    (net (code "71") (name "unconnected-(P2-Pad6)") (class "Default")
      (node (ref "P2") (pin "6") (pinfunction "6_6") (pintype "passive"))
    )
    (net (code "72") (name "unconnected-(P2-Pad7)") (class "Default")
      (node (ref "P2") (pin "7") (pinfunction "7_7") (pintype "passive"))
    )
    (net (code "73") (name "unconnected-(P2-Pad8)") (class "Default")
      (node (ref "P2") (pin "8") (pinfunction "8_8") (pintype "passive"))
    )
    (net (code "74") (name "unconnected-(P2-Pad9)") (class "Default")
      (node (ref "P2") (pin "9") (pinfunction "9_9") (pintype "passive"))
    )
    (net (code "75") (name "unconnected-(P2-Pad10)") (class "Default")
      (node (ref "P2") (pin "10") (pinfunction "10_10") (pintype "passive"))
    )
    (net (code "76") (name "unconnected-(P2-Pad11)") (class "Default")
      (node (ref "P2") (pin "11") (pinfunction "11_11") (pintype "passive"))
    )
    (net (code "77") (name "unconnected-(P2-Pad12)") (class "Default")
      (node (ref "P2") (pin "12") (pinfunction "12_12") (pintype "passive"))
    )
    (net (code "78") (name "unconnected-(P2-Pad13)") (class "Default")
      (node (ref "P2") (pin "13") (pinfunction "13_13") (pintype "passive"))
    )
    (net (code "79") (name "unconnected-(P2-Pad14)") (class "Default")
      (node (ref "P2") (pin "14") (pinfunction "14_14") (pintype "passive"))
    )
    (net (code "80") (name "unconnected-(P2-Pad15)") (class "Default")
      (node (ref "P2") (pin "15") (pinfunction "15_15") (pintype "passive"))
    )
    (net (code "81") (name "unconnected-(P2-Pad16)") (class "Default")
      (node (ref "P2") (pin "16") (pinfunction "16_16") (pintype "passive"))
    )
    (net (code "82") (name "unconnected-(P2-Pad17)") (class "Default")
      (node (ref "P2") (pin "17") (pinfunction "17_17") (pintype "passive"))
    )
    (net (code "83") (name "unconnected-(P2-Pad18)") (class "Default")
      (node (ref "P2") (pin "18") (pinfunction "18_18") (pintype "passive"))
    )
    (net (code "84") (name "unconnected-(P2-Pad19)") (class "Default")
      (node (ref "P2") (pin "19") (pinfunction "19_19") (pintype "passive"))
    )
    (net (code "85") (name "unconnected-(P2-Pad20)") (class "Default")
      (node (ref "P2") (pin "20") (pinfunction "20_20") (pintype "passive"))
    )
  )
)
